# lvds_receiver.net
KiCad netlist of a schematic drawn in EAGLE
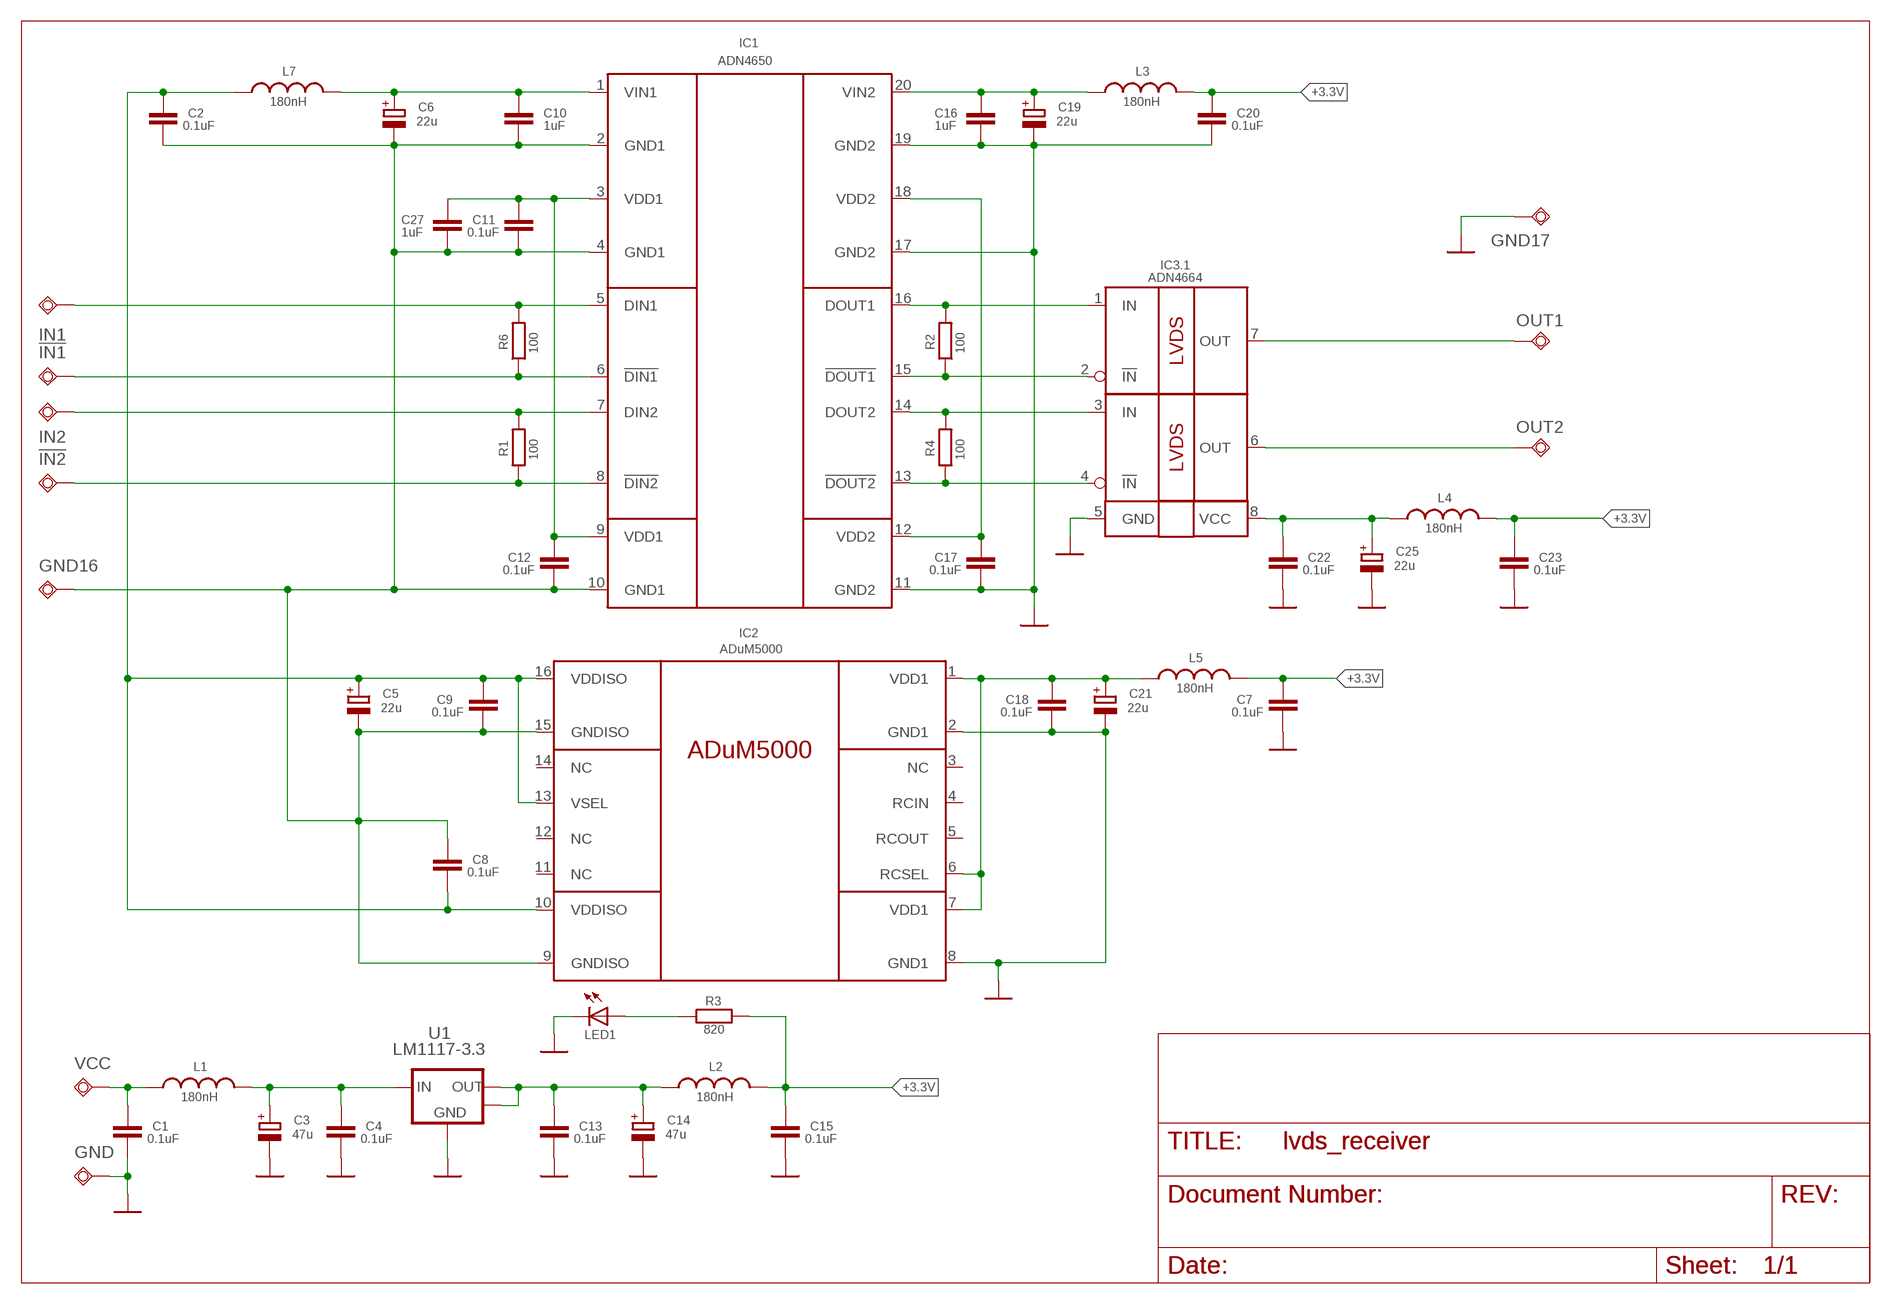
[diagram p0: schematic, sheet 1]

(export (version "E")
  (design (tool "Eeschema 10.0.6"))
  (components
    (comp (ref "!IN1")
      (value "TPSQTP20R")
      (footprint "eagle-import:TP20R")
      (libsource (lib "eagle-import") (part "TPSQTP20R"))
    )
    (comp (ref "!IN2")
      (value "TPSQTP20R")
      (footprint "eagle-import:TP20R")
      (libsource (lib "eagle-import") (part "TPSQTP20R"))
    )
    (comp (ref "C1")
      (value "0.1uF")
      (footprint "eagle-import:SMD0603")
      (libsource (lib "eagle-import") (part "C0603"))
    )
    (comp (ref "C2")
      (value "0.1uF")
      (footprint "eagle-import:SMD0603")
      (libsource (lib "eagle-import") (part "C0603"))
    )
    (comp (ref "C3")
      (value "47u")
      (footprint "eagle-import:SMC_C")
      (libsource (lib "eagle-import") (part "CPOL-EUSMCC"))
    )
    (comp (ref "C4")
      (value "0.1uF")
      (footprint "eagle-import:SMD0603")
      (libsource (lib "eagle-import") (part "C0603"))
    )
    (comp (ref "C5")
      (value "22u")
      (footprint "eagle-import:SMC_A")
      (libsource (lib "eagle-import") (part "CPOL-EUSMCA"))
    )
    (comp (ref "C6")
      (value "22u")
      (footprint "eagle-import:SMC_A")
      (libsource (lib "eagle-import") (part "CPOL-EUSMCA"))
    )
    (comp (ref "C7")
      (value "0.1uF")
      (footprint "eagle-import:SMD0603")
      (libsource (lib "eagle-import") (part "C0603"))
    )
    (comp (ref "C8")
      (value "0.1uF")
      (footprint "eagle-import:SMD0603")
      (libsource (lib "eagle-import") (part "C0603"))
    )
    (comp (ref "C9")
      (value "0.1uF")
      (footprint "eagle-import:SMD0603")
      (libsource (lib "eagle-import") (part "C0603"))
    )
    (comp (ref "C10")
      (value "1uF")
      (footprint "eagle-import:SMD0603")
      (libsource (lib "eagle-import") (part "C0603"))
    )
    (comp (ref "C11")
      (value "0.1uF")
      (footprint "eagle-import:SMD0603")
      (libsource (lib "eagle-import") (part "C0603"))
    )
    (comp (ref "C12")
      (value "0.1uF")
      (footprint "eagle-import:SMD0603")
      (libsource (lib "eagle-import") (part "C0603"))
    )
    (comp (ref "C13")
      (value "0.1uF")
      (footprint "eagle-import:SMD0603")
      (libsource (lib "eagle-import") (part "C0603"))
    )
    (comp (ref "C14")
      (value "47u")
      (footprint "eagle-import:SMC_C")
      (libsource (lib "eagle-import") (part "CPOL-EUSMCC"))
    )
    (comp (ref "C15")
      (value "0.1uF")
      (footprint "eagle-import:SMD0603")
      (libsource (lib "eagle-import") (part "C0603"))
    )
    (comp (ref "C16")
      (value "1uF")
      (footprint "eagle-import:SMD0603")
      (libsource (lib "eagle-import") (part "C0603"))
    )
    (comp (ref "C17")
      (value "0.1uF")
      (footprint "eagle-import:SMD0603")
      (libsource (lib "eagle-import") (part "C0603"))
    )
    (comp (ref "C18")
      (value "0.1uF")
      (footprint "eagle-import:SMD0603")
      (libsource (lib "eagle-import") (part "C0603"))
    )
    (comp (ref "C19")
      (value "22u")
      (footprint "eagle-import:SMC_A")
      (libsource (lib "eagle-import") (part "CPOL-EUSMCA"))
    )
    (comp (ref "C20")
      (value "0.1uF")
      (footprint "eagle-import:SMD0603")
      (libsource (lib "eagle-import") (part "C0603"))
    )
    (comp (ref "C21")
      (value "22u")
      (footprint "eagle-import:SMC_A")
      (libsource (lib "eagle-import") (part "CPOL-EUSMCA"))
    )
    (comp (ref "C22")
      (value "0.1uF")
      (footprint "eagle-import:SMD0603")
      (libsource (lib "eagle-import") (part "C0603"))
    )
    (comp (ref "C23")
      (value "0.1uF")
      (footprint "eagle-import:SMD0603")
      (libsource (lib "eagle-import") (part "C0603"))
    )
    (comp (ref "C25")
      (value "22u")
      (footprint "eagle-import:SMC_A")
      (libsource (lib "eagle-import") (part "CPOL-EUSMCA"))
    )
    (comp (ref "C27")
      (value "1uF")
      (footprint "eagle-import:SMD0603")
      (libsource (lib "eagle-import") (part "C0603"))
    )
    (comp (ref "GND")
      (value "TPSQTP20R")
      (footprint "eagle-import:TP20R")
      (libsource (lib "eagle-import") (part "TPSQTP20R"))
    )
    (comp (ref "GND16")
      (value "TPSQTP20R")
      (footprint "eagle-import:TP20R")
      (libsource (lib "eagle-import") (part "TPSQTP20R"))
    )
    (comp (ref "GND17")
      (value "TPSQTP20R")
      (footprint "eagle-import:TP20R")
      (libsource (lib "eagle-import") (part "TPSQTP20R"))
    )
    (comp (ref "IC1")
      (value "ADN4650")
      (footprint "eagle-import:SO20W")
      (libsource (lib "eagle-import") (part "ADN4650"))
    )
    (comp (ref "IC2")
      (value "ADuM5000")
      (footprint "eagle-import:SO16W")
      (libsource (lib "eagle-import") (part "ADUM5000"))
    )
    (comp (ref "IC3")
      (value "ADN4664")
      (footprint "eagle-import:SO08")
      (libsource (lib "eagle-import") (part "ADN4664"))
    )
    (comp (ref "IN1")
      (value "TPSQTP20R")
      (footprint "eagle-import:TP20R")
      (libsource (lib "eagle-import") (part "TPSQTP20R"))
    )
    (comp (ref "IN2")
      (value "TPSQTP20R")
      (footprint "eagle-import:TP20R")
      (libsource (lib "eagle-import") (part "TPSQTP20R"))
    )
    (comp (ref "L1")
      (value "180nH")
      (footprint "eagle-import:SMD0603")
      (libsource (lib "eagle-import") (part "L0603"))
    )
    (comp (ref "L2")
      (value "180nH")
      (footprint "eagle-import:SMD0603")
      (libsource (lib "eagle-import") (part "L0603"))
    )
    (comp (ref "L3")
      (value "180nH")
      (footprint "eagle-import:SMD0603")
      (libsource (lib "eagle-import") (part "L0603"))
    )
    (comp (ref "L4")
      (value "180nH")
      (footprint "eagle-import:SMD0603")
      (libsource (lib "eagle-import") (part "L0603"))
    )
    (comp (ref "L5")
      (value "180nH")
      (footprint "eagle-import:SMD0603")
      (libsource (lib "eagle-import") (part "L0603"))
    )
    (comp (ref "L7")
      (value "180nH")
      (footprint "eagle-import:SMD0603")
      (libsource (lib "eagle-import") (part "L0603"))
    )
    (comp (ref "LED1")
      (value "LEDCHIPLED_0805")
      (footprint "eagle-import:CHIPLED_0805")
      (libsource (lib "eagle-import") (part "LEDCHIPLED_0805"))
    )
    (comp (ref "OUT1")
      (value "TPSQTP20R")
      (footprint "eagle-import:TP20R")
      (libsource (lib "eagle-import") (part "TPSQTP20R"))
    )
    (comp (ref "OUT2")
      (value "TPSQTP20R")
      (footprint "eagle-import:TP20R")
      (libsource (lib "eagle-import") (part "TPSQTP20R"))
    )
    (comp (ref "R1")
      (value "100")
      (footprint "eagle-import:SMD0603")
      (libsource (lib "eagle-import") (part "R0603"))
    )
    (comp (ref "R2")
      (value "100")
      (footprint "eagle-import:SMD0603")
      (libsource (lib "eagle-import") (part "R0603"))
    )
    (comp (ref "R3")
      (value "820")
      (footprint "eagle-import:SMD0603")
      (libsource (lib "eagle-import") (part "R0603"))
    )
    (comp (ref "R4")
      (value "100")
      (footprint "eagle-import:SMD0603")
      (libsource (lib "eagle-import") (part "R0603"))
    )
    (comp (ref "R6")
      (value "100")
      (footprint "eagle-import:SMD0603")
      (libsource (lib "eagle-import") (part "R0603"))
    )
    (comp (ref "U1")
      (value "LM1117-3.3")
      (footprint "eagle-import:SOT223")
      (libsource (lib "eagle-import") (part "LM1117-3.3"))
    )
    (comp (ref "VCC")
      (value "TPSQTP20R")
      (footprint "eagle-import:TP20R")
      (libsource (lib "eagle-import") (part "TPSQTP20R"))
    )
  )
  (nets
    (net (code "1") (name "+3.3V") (class "Default")
      (node (ref "C15") (pin "1") (pinfunction "1_1") (pintype "passive"))
      (node (ref "C20") (pin "1") (pinfunction "1_1") (pintype "passive"))
      (node (ref "C23") (pin "1") (pinfunction "1_1") (pintype "passive"))
      (node (ref "C7") (pin "1") (pinfunction "1_1") (pintype "passive"))
      (node (ref "L2") (pin "2") (pinfunction "2_2") (pintype "passive"))
      (node (ref "L3") (pin "2") (pinfunction "2_2") (pintype "passive"))
      (node (ref "L4") (pin "2") (pinfunction "2_2") (pintype "passive"))
      (node (ref "L5") (pin "2") (pinfunction "2_2") (pintype "passive"))
      (node (ref "R3") (pin "2") (pinfunction "2_2") (pintype "passive"))
    )
    (net (code "2") (name "GND") (class "Default")
      (node (ref "C1") (pin "2") (pinfunction "2_2") (pintype "passive"))
      (node (ref "C13") (pin "2") (pinfunction "2_2") (pintype "passive"))
      (node (ref "C14") (pin "-") (pinfunction "-_-") (pintype "passive"))
      (node (ref "C15") (pin "2") (pinfunction "2_2") (pintype "passive"))
      (node (ref "C16") (pin "2") (pinfunction "2_2") (pintype "passive"))
      (node (ref "C17") (pin "2") (pinfunction "2_2") (pintype "passive"))
      (node (ref "C18") (pin "2") (pinfunction "2_2") (pintype "passive"))
      (node (ref "C19") (pin "-") (pinfunction "-_-") (pintype "passive"))
      (node (ref "C20") (pin "2") (pinfunction "2_2") (pintype "passive"))
      (node (ref "C21") (pin "-") (pinfunction "-_-") (pintype "passive"))
      (node (ref "C22") (pin "2") (pinfunction "2_2") (pintype "passive"))
      (node (ref "C23") (pin "2") (pinfunction "2_2") (pintype "passive"))
      (node (ref "C25") (pin "-") (pinfunction "-_-") (pintype "passive"))
      (node (ref "C3") (pin "-") (pinfunction "-_-") (pintype "passive"))
      (node (ref "C4") (pin "2") (pinfunction "2_2") (pintype "passive"))
      (node (ref "C7") (pin "2") (pinfunction "2_2") (pintype "passive"))
      (node (ref "GND") (pin "TP") (pinfunction "TP_TP") (pintype "input"))
      (node (ref "GND17") (pin "TP") (pinfunction "TP_TP") (pintype "input"))
      (node (ref "IC1") (pin "11") (pinfunction "GND2_11") (pintype "power_in"))
      (node (ref "IC1") (pin "17") (pinfunction "GND2_17") (pintype "power_in"))
      (node (ref "IC1") (pin "19") (pinfunction "GND2_19") (pintype "power_in"))
      (node (ref "IC2") (pin "2") (pinfunction "GND1_2") (pintype "power_in"))
      (node (ref "IC2") (pin "8") (pinfunction "GND1_8") (pintype "power_in"))
      (node (ref "IC3") (pin "5") (pinfunction "GND_5") (pintype "power_in"))
      (node (ref "LED1") (pin "C") (pinfunction "C_C") (pintype "passive"))
      (node (ref "U1") (pin "1") (pinfunction "GND_1") (pintype "power_in"))
    )
    (net (code "3") (name "Net-(C1-Pad1)") (class "Default")
      (node (ref "C1") (pin "1") (pinfunction "1_1") (pintype "passive"))
      (node (ref "L1") (pin "1") (pinfunction "1_1") (pintype "passive"))
      (node (ref "VCC") (pin "TP") (pinfunction "TP_TP") (pintype "input"))
    )
    (net (code "4") (name "Net-(C10-Pad2)") (class "Default")
      (node (ref "C10") (pin "2") (pinfunction "2_2") (pintype "passive"))
      (node (ref "C11") (pin "2") (pinfunction "2_2") (pintype "passive"))
      (node (ref "C12") (pin "2") (pinfunction "2_2") (pintype "passive"))
      (node (ref "C2") (pin "2") (pinfunction "2_2") (pintype "passive"))
      (node (ref "C27") (pin "2") (pinfunction "2_2") (pintype "passive"))
      (node (ref "C5") (pin "-") (pinfunction "-_-") (pintype "passive"))
      (node (ref "C6") (pin "-") (pinfunction "-_-") (pintype "passive"))
      (node (ref "C8") (pin "1") (pinfunction "1_1") (pintype "passive"))
      (node (ref "C9") (pin "2") (pinfunction "2_2") (pintype "passive"))
      (node (ref "GND16") (pin "TP") (pinfunction "TP_TP") (pintype "input"))
      (node (ref "IC1") (pin "10") (pinfunction "GND1_10") (pintype "power_in"))
      (node (ref "IC1") (pin "2") (pinfunction "GND1_2") (pintype "power_in"))
      (node (ref "IC1") (pin "4") (pinfunction "GND1_4") (pintype "power_in"))
      (node (ref "IC2") (pin "15") (pinfunction "GNDISO_15") (pintype "power_in"))
      (node (ref "IC2") (pin "9") (pinfunction "GNDISO_9") (pintype "power_in"))
    )
    (net (code "5") (name "Net-(C11-Pad1)") (class "Default")
      (node (ref "C11") (pin "1") (pinfunction "1_1") (pintype "passive"))
      (node (ref "C12") (pin "1") (pinfunction "1_1") (pintype "passive"))
      (node (ref "C27") (pin "1") (pinfunction "1_1") (pintype "passive"))
      (node (ref "IC1") (pin "3") (pinfunction "VDD1_3") (pintype "power_in"))
      (node (ref "IC1") (pin "9") (pinfunction "VDD1_9") (pintype "power_in"))
    )
    (net (code "6") (name "Net-(C17-Pad1)") (class "Default")
      (node (ref "C17") (pin "1") (pinfunction "1_1") (pintype "passive"))
      (node (ref "IC1") (pin "12") (pinfunction "VDD2_12") (pintype "power_in"))
      (node (ref "IC1") (pin "18") (pinfunction "VDD2_18") (pintype "power_in"))
    )
    (net (code "7") (name "Net-(IC1-DIN1)") (class "Default")
      (node (ref "IC1") (pin "5") (pinfunction "DIN1_5") (pintype "input"))
      (node (ref "IN1") (pin "TP") (pinfunction "TP_TP") (pintype "input"))
      (node (ref "R6") (pin "2") (pinfunction "2_2") (pintype "passive"))
    )
    (net (code "8") (name "Net-(IC1-DIN2)") (class "Default")
      (node (ref "IC1") (pin "7") (pinfunction "DIN2_7") (pintype "input"))
      (node (ref "IN2") (pin "TP") (pinfunction "TP_TP") (pintype "input"))
      (node (ref "R1") (pin "2") (pinfunction "2_2") (pintype "passive"))
    )
    (net (code "9") (name "Net-(IC1-DOUT1)") (class "Default")
      (node (ref "IC1") (pin "16") (pinfunction "DOUT1_16") (pintype "output"))
      (node (ref "IC3") (pin "1") (pinfunction "IN_1") (pintype "input"))
      (node (ref "R2") (pin "2") (pinfunction "2_2") (pintype "passive"))
    )
    (net (code "10") (name "Net-(IC1-DOUT2)") (class "Default")
      (node (ref "IC1") (pin "14") (pinfunction "DOUT2_14") (pintype "output"))
      (node (ref "IC3") (pin "3") (pinfunction "IN_3") (pintype "input"))
      (node (ref "R4") (pin "2") (pinfunction "2_2") (pintype "passive"))
    )
    (net (code "11") (name "Net-(IC1-VIN1)") (class "Default")
      (node (ref "C10") (pin "1") (pinfunction "1_1") (pintype "passive"))
      (node (ref "C6") (pin "+") (pinfunction "+_+") (pintype "passive"))
      (node (ref "IC1") (pin "1") (pinfunction "VIN1_1") (pintype "power_in"))
      (node (ref "L7") (pin "2") (pinfunction "2_2") (pintype "passive"))
    )
    (net (code "12") (name "Net-(IC1-VIN2)") (class "Default")
      (node (ref "C16") (pin "1") (pinfunction "1_1") (pintype "passive"))
      (node (ref "C19") (pin "+") (pinfunction "+_+") (pintype "passive"))
      (node (ref "IC1") (pin "20") (pinfunction "VIN2_20") (pintype "power_in"))
      (node (ref "L3") (pin "1") (pinfunction "1_1") (pintype "passive"))
    )
    (net (code "13") (name "Net-(IC1-~{DIN1})") (class "Default")
      (node (ref "!IN1") (pin "TP") (pinfunction "TP_TP") (pintype "input"))
      (node (ref "IC1") (pin "6") (pinfunction "~{DIN1}_6") (pintype "input"))
      (node (ref "R6") (pin "1") (pinfunction "1_1") (pintype "passive"))
    )
    (net (code "14") (name "Net-(IC1-~{DIN2})") (class "Default")
      (node (ref "!IN2") (pin "TP") (pinfunction "TP_TP") (pintype "input"))
      (node (ref "IC1") (pin "8") (pinfunction "~{DIN2}_8") (pintype "input"))
      (node (ref "R1") (pin "1") (pinfunction "1_1") (pintype "passive"))
    )
    (net (code "15") (name "Net-(IC1-~{DOUT1})") (class "Default")
      (node (ref "IC1") (pin "15") (pinfunction "~{DOUT1}_15") (pintype "output"))
      (node (ref "IC3") (pin "2") (pinfunction "~{IN}_2") (pintype "input"))
      (node (ref "R2") (pin "1") (pinfunction "1_1") (pintype "passive"))
    )
    (net (code "16") (name "Net-(IC1-~{DOUT2})") (class "Default")
      (node (ref "IC1") (pin "13") (pinfunction "~{DOUT2}_13") (pintype "output"))
      (node (ref "IC3") (pin "4") (pinfunction "~{IN}_4") (pintype "input"))
      (node (ref "R4") (pin "1") (pinfunction "1_1") (pintype "passive"))
    )
    (net (code "17") (name "Net-(IC2-RCSEL)") (class "Default")
      (node (ref "C18") (pin "1") (pinfunction "1_1") (pintype "passive"))
      (node (ref "C21") (pin "+") (pinfunction "+_+") (pintype "passive"))
      (node (ref "IC2") (pin "1") (pinfunction "VDD1_1") (pintype "power_in"))
      (node (ref "IC2") (pin "6") (pinfunction "RCSEL_6") (pintype "input"))
      (node (ref "IC2") (pin "7") (pinfunction "VDD1_7") (pintype "power_in"))
      (node (ref "L5") (pin "1") (pinfunction "1_1") (pintype "passive"))
    )
    (net (code "18") (name "Net-(IC2-VSEL)") (class "Default")
      (node (ref "C2") (pin "1") (pinfunction "1_1") (pintype "passive"))
      (node (ref "C5") (pin "+") (pinfunction "+_+") (pintype "passive"))
      (node (ref "C8") (pin "2") (pinfunction "2_2") (pintype "passive"))
      (node (ref "C9") (pin "1") (pinfunction "1_1") (pintype "passive"))
      (node (ref "IC2") (pin "10") (pinfunction "VDDISO_10") (pintype "power_in"))
      (node (ref "IC2") (pin "13") (pinfunction "VSEL_13") (pintype "power_in"))
      (node (ref "IC2") (pin "16") (pinfunction "VDDISO_16") (pintype "power_in"))
      (node (ref "L7") (pin "1") (pinfunction "1_1") (pintype "passive"))
    )
    (net (code "19") (name "Net-(IC3A-OUT)") (class "Default")
      (node (ref "IC3") (pin "7") (pinfunction "OUT_7") (pintype "output"))
      (node (ref "OUT1") (pin "TP") (pinfunction "TP_TP") (pintype "input"))
    )
    (net (code "20") (name "Net-(IC3B-OUT)") (class "Default")
      (node (ref "IC3") (pin "6") (pinfunction "OUT_6") (pintype "output"))
      (node (ref "OUT2") (pin "TP") (pinfunction "TP_TP") (pintype "input"))
    )
    (net (code "21") (name "Net-(IC3C-VCC)") (class "Default")
      (node (ref "C22") (pin "1") (pinfunction "1_1") (pintype "passive"))
      (node (ref "C25") (pin "+") (pinfunction "+_+") (pintype "passive"))
      (node (ref "IC3") (pin "8") (pinfunction "VCC_8") (pintype "power_in"))
      (node (ref "L4") (pin "1") (pinfunction "1_1") (pintype "passive"))
    )
    (net (code "22") (name "Net-(LED1-PadA)") (class "Default")
      (node (ref "LED1") (pin "A") (pinfunction "A_A") (pintype "passive"))
      (node (ref "R3") (pin "1") (pinfunction "1_1") (pintype "passive"))
    )
    (net (code "23") (name "Net-(U1-IN)") (class "Default")
      (node (ref "C3") (pin "+") (pinfunction "+_+") (pintype "passive"))
      (node (ref "C4") (pin "1") (pinfunction "1_1") (pintype "passive"))
      (node (ref "L1") (pin "2") (pinfunction "2_2") (pintype "passive"))
      (node (ref "U1") (pin "3") (pinfunction "IN_3") (pintype "power_in"))
    )
    (net (code "24") (name "Net-(U1-MASS)") (class "Default")
      (node (ref "C13") (pin "1") (pinfunction "1_1") (pintype "passive"))
      (node (ref "C14") (pin "+") (pinfunction "+_+") (pintype "passive"))
      (node (ref "L2") (pin "1") (pinfunction "1_1") (pintype "passive"))
      (node (ref "U1") (pin "2") (pinfunction "OUT_2") (pintype "power_in"))
      (node (ref "U1") (pin "4") (pinfunction "MASS_4") (pintype "passive"))
    )
    (net (code "25") (name "unconnected-(IC2-NC-Pad3)") (class "Default")
      (node (ref "IC2") (pin "3") (pinfunction "NC_3") (pintype "no_connect"))
    )
    (net (code "26") (name "unconnected-(IC2-NC-Pad11)") (class "Default")
      (node (ref "IC2") (pin "11") (pinfunction "NC_11") (pintype "no_connect"))
    )
    (net (code "27") (name "unconnected-(IC2-NC-Pad12)") (class "Default")
      (node (ref "IC2") (pin "12") (pinfunction "NC_12") (pintype "no_connect"))
    )
    (net (code "28") (name "unconnected-(IC2-NC-Pad14)") (class "Default")
      (node (ref "IC2") (pin "14") (pinfunction "NC_14") (pintype "no_connect"))
    )
    (net (code "29") (name "unconnected-(IC2-RCIN-Pad4)") (class "Default")
      (node (ref "IC2") (pin "4") (pinfunction "RCIN_4") (pintype "input"))
    )
    (net (code "30") (name "unconnected-(IC2-RCOUT-Pad5)") (class "Default")
      (node (ref "IC2") (pin "5") (pinfunction "RCOUT_5") (pintype "output"))
    )
  )
)
